# G1000_Arduino_Breakout_and_MCPs.net
KiCad netlist of a schematic drawn in EAGLE
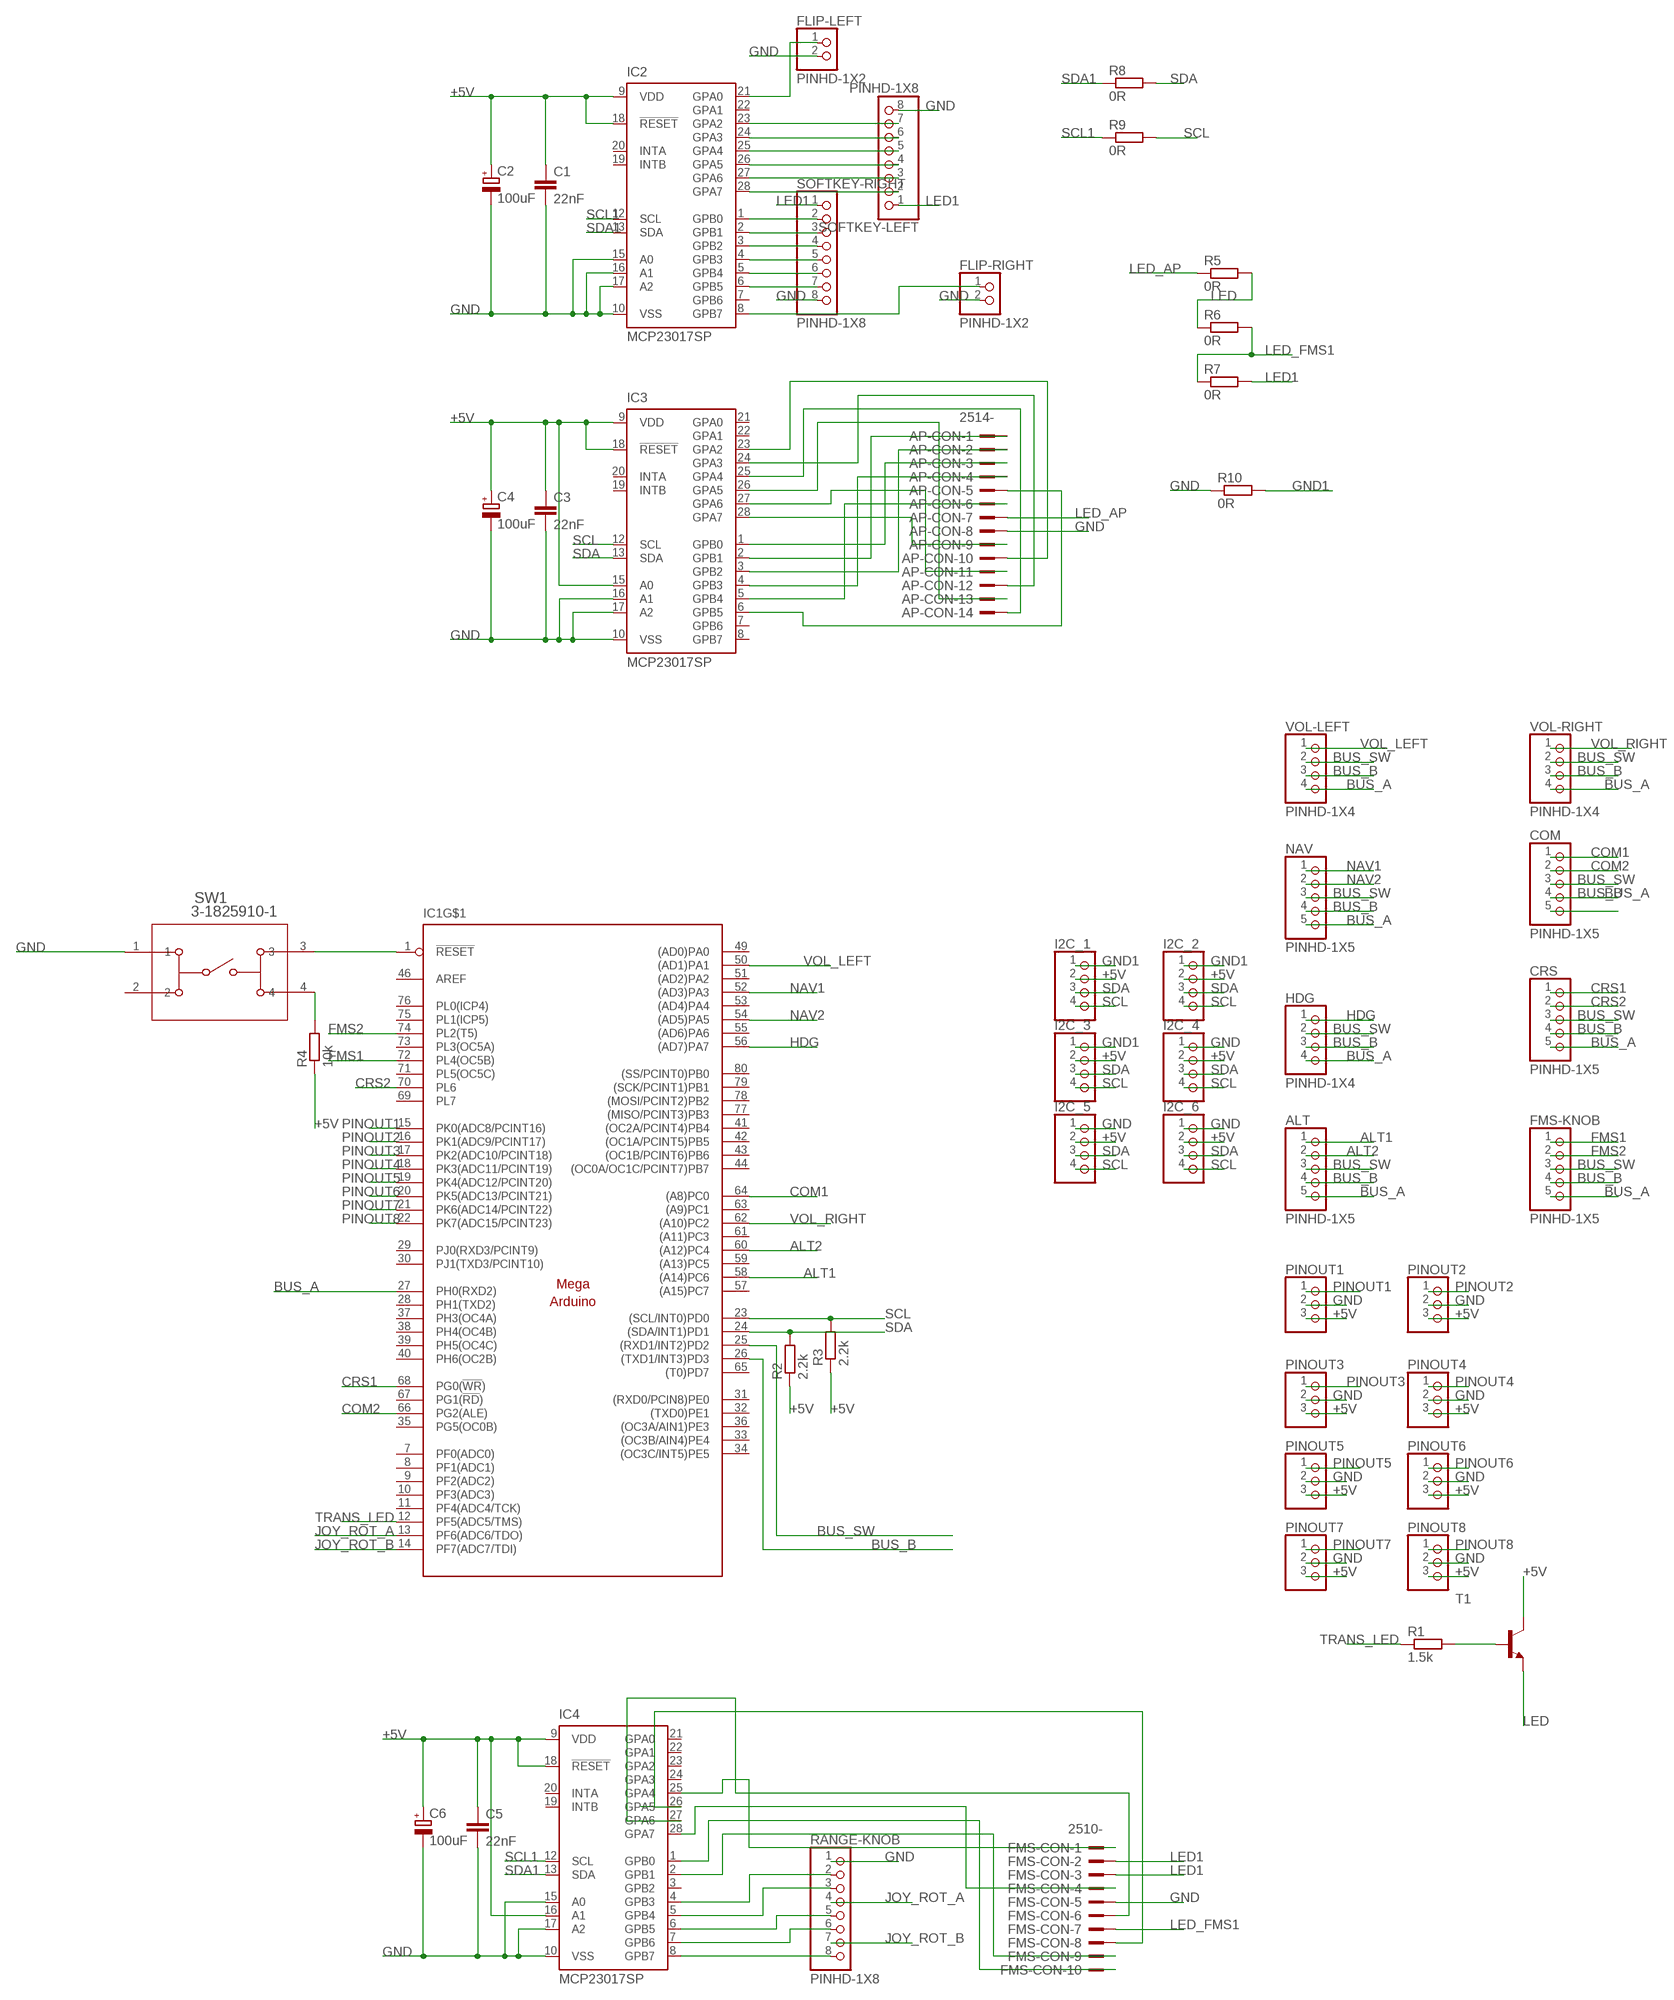
[diagram p0: schematic, sheet 1]

(export (version "E")
  (design (tool "Eeschema 10.0.6"))
  (components
    (comp (ref "ALT")
      (value "PINHD-1X5")
      (footprint "eagle-import:1X05")
      (libsource (lib "eagle-import") (part "PINHD-1X5"))
    )
    (comp (ref "AP-CON")
      (value "2514-")
      (footprint "eagle-import:PAK100_2500-14")
      (libsource (lib "eagle-import") (part "2514-"))
    )
    (comp (ref "C1")
      (value "22nF")
      (footprint "eagle-import:C025-025X050")
      (libsource (lib "eagle-import") (part "C-EU025-025X050"))
    )
    (comp (ref "C2")
      (value "100uF")
      (footprint "eagle-import:E2,5-6")
      (libsource (lib "eagle-import") (part "CPOL-EUE2.5-6"))
    )
    (comp (ref "C3")
      (value "22nF")
      (footprint "eagle-import:C025-025X050")
      (libsource (lib "eagle-import") (part "C-EU025-025X050"))
    )
    (comp (ref "C4")
      (value "100uF")
      (footprint "eagle-import:E2,5-6")
      (libsource (lib "eagle-import") (part "CPOL-EUE2.5-6"))
    )
    (comp (ref "C5")
      (value "22nF")
      (footprint "eagle-import:C025-025X050")
      (libsource (lib "eagle-import") (part "C-EU025-025X050"))
    )
    (comp (ref "C6")
      (value "100uF")
      (footprint "eagle-import:E2,5-6")
      (libsource (lib "eagle-import") (part "CPOL-EUE2.5-6"))
    )
    (comp (ref "COM")
      (value "PINHD-1X5")
      (footprint "eagle-import:1X05")
      (libsource (lib "eagle-import") (part "PINHD-1X5"))
    )
    (comp (ref "CRS")
      (value "PINHD-1X5")
      (footprint "eagle-import:1X05")
      (libsource (lib "eagle-import") (part "PINHD-1X5"))
    )
    (comp (ref "FLIP-LEFT")
      (value "PINHD-1X2")
      (footprint "eagle-import:1X02")
      (libsource (lib "eagle-import") (part "PINHD-1X2"))
    )
    (comp (ref "FLIP-RIGHT")
      (value "PINHD-1X2")
      (footprint "eagle-import:1X02")
      (libsource (lib "eagle-import") (part "PINHD-1X2"))
    )
    (comp (ref "FMS-CON")
      (value "2510-")
      (footprint "eagle-import:PAK100_2500-10")
      (fields (field (name "MF") "3M") (field (name "MPN") "2510-6002UB"))
      (libsource (lib "eagle-import") (part "2510-"))
    )
    (comp (ref "FMS-KNOB")
      (value "PINHD-1X5")
      (footprint "eagle-import:1X05")
      (libsource (lib "eagle-import") (part "PINHD-1X5"))
    )
    (comp (ref "HDG")
      (value "PINHD-1X4")
      (footprint "eagle-import:1X04")
      (libsource (lib "eagle-import") (part "PINHD-1X4"))
    )
    (comp (ref "I2C_1")
      (value "PINHD-1X4")
      (footprint "eagle-import:1X04")
      (libsource (lib "eagle-import") (part "pinhead_325_PINHD-1X4"))
    )
    (comp (ref "I2C_2")
      (value "PINHD-1X4")
      (footprint "eagle-import:1X04")
      (libsource (lib "eagle-import") (part "pinhead_325_PINHD-1X4"))
    )
    (comp (ref "I2C_3")
      (value "PINHD-1X4")
      (footprint "eagle-import:1X04")
      (libsource (lib "eagle-import") (part "pinhead_325_PINHD-1X4"))
    )
    (comp (ref "I2C_4")
      (value "PINHD-1X4")
      (footprint "eagle-import:1X04")
      (libsource (lib "eagle-import") (part "pinhead_325_PINHD-1X4"))
    )
    (comp (ref "I2C_5")
      (value "PINHD-1X4")
      (footprint "eagle-import:1X04")
      (libsource (lib "eagle-import") (part "pinhead_325_PINHD-1X4"))
    )
    (comp (ref "I2C_6")
      (value "PINHD-1X4")
      (footprint "eagle-import:1X04")
      (libsource (lib "eagle-import") (part "pinhead_325_PINHD-1X4"))
    )
    (comp (ref "IC1")
      (value "MEGAARDUINO_22")
      (footprint "eagle-import:MEGA_ARDUINO_2")
      (libsource (lib "eagle-import") (part "MEGAARDUINO_22"))
    )
    (comp (ref "IC2")
      (value "MCP23017SP")
      (footprint "eagle-import:DIL28-3")
      (libsource (lib "eagle-import") (part "MCP23017SP"))
    )
    (comp (ref "IC3")
      (value "MCP23017SP")
      (footprint "eagle-import:DIL28-3")
      (libsource (lib "eagle-import") (part "MCP23017SP"))
    )
    (comp (ref "IC4")
      (value "MCP23017SP")
      (footprint "eagle-import:DIL28-3")
      (libsource (lib "eagle-import") (part "MCP23017SP"))
    )
    (comp (ref "NAV")
      (value "PINHD-1X5")
      (footprint "eagle-import:1X05")
      (libsource (lib "eagle-import") (part "PINHD-1X5"))
    )
    (comp (ref "PINOUT1")
      (value "PINHD-1X3")
      (footprint "eagle-import:1X03")
      (libsource (lib "eagle-import") (part "PINHD-1X3"))
    )
    (comp (ref "PINOUT2")
      (value "PINHD-1X3")
      (footprint "eagle-import:1X03")
      (libsource (lib "eagle-import") (part "PINHD-1X3"))
    )
    (comp (ref "PINOUT3")
      (value "PINHD-1X3")
      (footprint "eagle-import:1X03")
      (libsource (lib "eagle-import") (part "PINHD-1X3"))
    )
    (comp (ref "PINOUT4")
      (value "PINHD-1X3")
      (footprint "eagle-import:1X03")
      (libsource (lib "eagle-import") (part "PINHD-1X3"))
    )
    (comp (ref "PINOUT5")
      (value "PINHD-1X3")
      (footprint "eagle-import:1X03")
      (libsource (lib "eagle-import") (part "PINHD-1X3"))
    )
    (comp (ref "PINOUT6")
      (value "PINHD-1X3")
      (footprint "eagle-import:1X03")
      (libsource (lib "eagle-import") (part "PINHD-1X3"))
    )
    (comp (ref "PINOUT7")
      (value "PINHD-1X3")
      (footprint "eagle-import:1X03")
      (libsource (lib "eagle-import") (part "PINHD-1X3"))
    )
    (comp (ref "PINOUT8")
      (value "PINHD-1X3")
      (footprint "eagle-import:1X03")
      (libsource (lib "eagle-import") (part "PINHD-1X3"))
    )
    (comp (ref "R1")
      (value "1.5k")
      (footprint "eagle-import:0207_10")
      (libsource (lib "eagle-import") (part "R-EU_0207/10"))
    )
    (comp (ref "R2")
      (value "2.2k")
      (footprint "eagle-import:0207_10")
      (libsource (lib "eagle-import") (part "R-EU_0207/10"))
    )
    (comp (ref "R3")
      (value "2.2k")
      (footprint "eagle-import:0207_10")
      (libsource (lib "eagle-import") (part "R-EU_0207/10"))
    )
    (comp (ref "R4")
      (value "10k")
      (footprint "eagle-import:0207_10")
      (libsource (lib "eagle-import") (part "R-EU_0207/10"))
    )
    (comp (ref "R5")
      (value "0R")
      (footprint "eagle-import:0207_10")
      (libsource (lib "eagle-import") (part "R-EU_0207/10"))
    )
    (comp (ref "R6")
      (value "0R")
      (footprint "eagle-import:0207_10")
      (libsource (lib "eagle-import") (part "R-EU_0207/10"))
    )
    (comp (ref "R7")
      (value "0R")
      (footprint "eagle-import:0207_10")
      (libsource (lib "eagle-import") (part "R-EU_0207/10"))
    )
    (comp (ref "R8")
      (value "0R")
      (footprint "eagle-import:0207_10")
      (libsource (lib "eagle-import") (part "R-EU_0207/10"))
    )
    (comp (ref "R9")
      (value "0R")
      (footprint "eagle-import:0207_10")
      (libsource (lib "eagle-import") (part "R-EU_0207/10"))
    )
    (comp (ref "R10")
      (value "0R")
      (footprint "eagle-import:0207_10")
      (libsource (lib "eagle-import") (part "R-EU_0207/10"))
    )
    (comp (ref "RANGE-KNOB")
      (value "PINHD-1X8")
      (footprint "eagle-import:1X08")
      (libsource (lib "eagle-import") (part "PINHD-1X8"))
    )
    (comp (ref "SOFTKEY-LEFT")
      (value "PINHD-1X8")
      (footprint "eagle-import:1X08")
      (libsource (lib "eagle-import") (part "PINHD-1X8"))
    )
    (comp (ref "SOFTKEY-RIGHT")
      (value "PINHD-1X8")
      (footprint "eagle-import:1X08")
      (libsource (lib "eagle-import") (part "PINHD-1X8"))
    )
    (comp (ref "SW1")
      (value "3-1825910-1")
      (footprint "eagle-import:SW4_1825910-H")
      (fields (field (name "COPYRIGHT") "Copyright (C) 2016 Accelerated Designs. All rights reserved"))
      (libsource (lib "eagle-import") (part "3-1825910-1"))
    )
    (comp (ref "T1")
      (value "2N2222-NPN-TO92-EBC")
      (footprint "eagle-import:TO92-EBC")
      (libsource (lib "eagle-import") (part "-NPN-TO92-EBC2N2222"))
    )
    (comp (ref "VOL-LEFT")
      (value "PINHD-1X4")
      (footprint "eagle-import:1X04")
      (libsource (lib "eagle-import") (part "PINHD-1X4"))
    )
    (comp (ref "VOL-RIGHT")
      (value "PINHD-1X4")
      (footprint "eagle-import:1X04")
      (libsource (lib "eagle-import") (part "PINHD-1X4"))
    )
  )
  (nets
    (net (code "1") (name "/+5V") (class "Default")
      (node (ref "C1") (pin "1") (pinfunction "1_1") (pintype "passive"))
      (node (ref "C2") (pin "+") (pinfunction "+_+") (pintype "passive"))
      (node (ref "C3") (pin "1") (pinfunction "1_1") (pintype "passive"))
      (node (ref "C4") (pin "+") (pinfunction "+_+") (pintype "passive"))
      (node (ref "C5") (pin "1") (pinfunction "1_1") (pintype "passive"))
      (node (ref "C6") (pin "+") (pinfunction "+_+") (pintype "passive"))
      (node (ref "I2C_1") (pin "2") (pinfunction "2_2") (pintype "passive"))
      (node (ref "I2C_2") (pin "2") (pinfunction "2_2") (pintype "passive"))
      (node (ref "I2C_3") (pin "2") (pinfunction "2_2") (pintype "passive"))
      (node (ref "I2C_4") (pin "2") (pinfunction "2_2") (pintype "passive"))
      (node (ref "I2C_5") (pin "2") (pinfunction "2_2") (pintype "passive"))
      (node (ref "I2C_6") (pin "2") (pinfunction "2_2") (pintype "passive"))
      (node (ref "IC2") (pin "18") (pinfunction "~{RESET}_18") (pintype "input"))
      (node (ref "IC2") (pin "9") (pinfunction "VDD_9") (pintype "power_in"))
      (node (ref "IC3") (pin "15") (pinfunction "A0_15") (pintype "input"))
      (node (ref "IC3") (pin "18") (pinfunction "~{RESET}_18") (pintype "input"))
      (node (ref "IC3") (pin "9") (pinfunction "VDD_9") (pintype "power_in"))
      (node (ref "IC4") (pin "16") (pinfunction "A1_16") (pintype "input"))
      (node (ref "IC4") (pin "18") (pinfunction "~{RESET}_18") (pintype "input"))
      (node (ref "IC4") (pin "9") (pinfunction "VDD_9") (pintype "power_in"))
      (node (ref "PINOUT1") (pin "3") (pinfunction "3_3") (pintype "passive"))
      (node (ref "PINOUT2") (pin "3") (pinfunction "3_3") (pintype "passive"))
      (node (ref "PINOUT3") (pin "3") (pinfunction "3_3") (pintype "passive"))
      (node (ref "PINOUT4") (pin "3") (pinfunction "3_3") (pintype "passive"))
      (node (ref "PINOUT5") (pin "3") (pinfunction "3_3") (pintype "passive"))
      (node (ref "PINOUT6") (pin "3") (pinfunction "3_3") (pintype "passive"))
      (node (ref "PINOUT7") (pin "3") (pinfunction "3_3") (pintype "passive"))
      (node (ref "PINOUT8") (pin "3") (pinfunction "3_3") (pintype "passive"))
      (node (ref "R2") (pin "1") (pinfunction "1_1") (pintype "passive"))
      (node (ref "R3") (pin "1") (pinfunction "1_1") (pintype "passive"))
      (node (ref "R4") (pin "1") (pinfunction "1_1") (pintype "passive"))
      (node (ref "T1") (pin "C") (pinfunction "C_C") (pintype "passive"))
    )
    (net (code "2") (name "/ALT1") (class "Default")
      (node (ref "ALT") (pin "1") (pinfunction "1_1") (pintype "passive"))
      (node (ref "IC1") (pin "58") (pinfunction "(A14)PC6_58") (pintype "bidirectional"))
    )
    (net (code "3") (name "/ALT2") (class "Default")
      (node (ref "ALT") (pin "2") (pinfunction "2_2") (pintype "passive"))
      (node (ref "IC1") (pin "60") (pinfunction "(A12)PC4_60") (pintype "bidirectional"))
    )
    (net (code "4") (name "/BUS_A") (class "Default")
      (node (ref "ALT") (pin "5") (pinfunction "5_5") (pintype "passive"))
      (node (ref "COM") (pin "5") (pinfunction "5_5") (pintype "passive"))
      (node (ref "CRS") (pin "5") (pinfunction "5_5") (pintype "passive"))
      (node (ref "FMS-KNOB") (pin "5") (pinfunction "5_5") (pintype "passive"))
      (node (ref "HDG") (pin "4") (pinfunction "4_4") (pintype "passive"))
      (node (ref "IC1") (pin "27") (pinfunction "PH0(RXD2)_27") (pintype "bidirectional"))
      (node (ref "NAV") (pin "5") (pinfunction "5_5") (pintype "passive"))
      (node (ref "VOL-LEFT") (pin "4") (pinfunction "4_4") (pintype "passive"))
      (node (ref "VOL-RIGHT") (pin "4") (pinfunction "4_4") (pintype "passive"))
    )
    (net (code "5") (name "/BUS_B") (class "Default")
      (node (ref "ALT") (pin "4") (pinfunction "4_4") (pintype "passive"))
      (node (ref "COM") (pin "4") (pinfunction "4_4") (pintype "passive"))
      (node (ref "CRS") (pin "4") (pinfunction "4_4") (pintype "passive"))
      (node (ref "FMS-KNOB") (pin "4") (pinfunction "4_4") (pintype "passive"))
      (node (ref "HDG") (pin "3") (pinfunction "3_3") (pintype "passive"))
      (node (ref "IC1") (pin "26") (pinfunction "(TXD1/INT3)PD3_26") (pintype "bidirectional"))
      (node (ref "NAV") (pin "4") (pinfunction "4_4") (pintype "passive"))
      (node (ref "VOL-LEFT") (pin "3") (pinfunction "3_3") (pintype "passive"))
      (node (ref "VOL-RIGHT") (pin "3") (pinfunction "3_3") (pintype "passive"))
    )
    (net (code "6") (name "/BUS_SW") (class "Default")
      (node (ref "ALT") (pin "3") (pinfunction "3_3") (pintype "passive"))
      (node (ref "COM") (pin "3") (pinfunction "3_3") (pintype "passive"))
      (node (ref "CRS") (pin "3") (pinfunction "3_3") (pintype "passive"))
      (node (ref "FMS-KNOB") (pin "3") (pinfunction "3_3") (pintype "passive"))
      (node (ref "HDG") (pin "2") (pinfunction "2_2") (pintype "passive"))
      (node (ref "IC1") (pin "25") (pinfunction "(RXD1/INT2)PD2_25") (pintype "bidirectional"))
      (node (ref "NAV") (pin "3") (pinfunction "3_3") (pintype "passive"))
      (node (ref "VOL-LEFT") (pin "2") (pinfunction "2_2") (pintype "passive"))
      (node (ref "VOL-RIGHT") (pin "2") (pinfunction "2_2") (pintype "passive"))
    )
    (net (code "7") (name "/COM1") (class "Default")
      (node (ref "COM") (pin "1") (pinfunction "1_1") (pintype "passive"))
      (node (ref "IC1") (pin "64") (pinfunction "(A8)PC0_64") (pintype "bidirectional"))
    )
    (net (code "8") (name "/COM2") (class "Default")
      (node (ref "COM") (pin "2") (pinfunction "2_2") (pintype "passive"))
      (node (ref "IC1") (pin "66") (pinfunction "PG2(ALE)_66") (pintype "bidirectional"))
    )
    (net (code "9") (name "/CRS1") (class "Default")
      (node (ref "CRS") (pin "1") (pinfunction "1_1") (pintype "passive"))
      (node (ref "IC1") (pin "68") (pinfunction "PG0(~{WR})_68") (pintype "bidirectional"))
    )
    (net (code "10") (name "/CRS2") (class "Default")
      (node (ref "CRS") (pin "2") (pinfunction "2_2") (pintype "passive"))
      (node (ref "IC1") (pin "70") (pinfunction "PL6_70") (pintype "bidirectional"))
    )
    (net (code "11") (name "/FMS1") (class "Default")
      (node (ref "FMS-KNOB") (pin "1") (pinfunction "1_1") (pintype "passive"))
      (node (ref "IC1") (pin "72") (pinfunction "PL4(OC5B)_72") (pintype "bidirectional"))
    )
    (net (code "12") (name "/FMS2") (class "Default")
      (node (ref "FMS-KNOB") (pin "2") (pinfunction "2_2") (pintype "passive"))
      (node (ref "IC1") (pin "74") (pinfunction "PL2(T5)_74") (pintype "bidirectional"))
    )
    (net (code "13") (name "/GND") (class "Default")
      (node (ref "AP-CON") (pin "8") (pinfunction "KL_8") (pintype "passive"))
      (node (ref "C1") (pin "2") (pinfunction "2_2") (pintype "passive"))
      (node (ref "C2") (pin "-") (pinfunction "-_-") (pintype "passive"))
      (node (ref "C3") (pin "2") (pinfunction "2_2") (pintype "passive"))
      (node (ref "C4") (pin "-") (pinfunction "-_-") (pintype "passive"))
      (node (ref "C5") (pin "2") (pinfunction "2_2") (pintype "passive"))
      (node (ref "C6") (pin "-") (pinfunction "-_-") (pintype "passive"))
      (node (ref "FLIP-LEFT") (pin "2") (pinfunction "2_2") (pintype "passive"))
      (node (ref "FLIP-RIGHT") (pin "2") (pinfunction "2_2") (pintype "passive"))
      (node (ref "FMS-CON") (pin "5") (pinfunction "KL_5") (pintype "passive"))
      (node (ref "I2C_4") (pin "1") (pinfunction "1_1") (pintype "passive"))
      (node (ref "I2C_5") (pin "1") (pinfunction "1_1") (pintype "passive"))
      (node (ref "I2C_6") (pin "1") (pinfunction "1_1") (pintype "passive"))
      (node (ref "IC2") (pin "10") (pinfunction "VSS_10") (pintype "power_in"))
      (node (ref "IC2") (pin "15") (pinfunction "A0_15") (pintype "input"))
      (node (ref "IC2") (pin "16") (pinfunction "A1_16") (pintype "input"))
      (node (ref "IC2") (pin "17") (pinfunction "A2_17") (pintype "input"))
      (node (ref "IC3") (pin "10") (pinfunction "VSS_10") (pintype "power_in"))
      (node (ref "IC3") (pin "16") (pinfunction "A1_16") (pintype "input"))
      (node (ref "IC3") (pin "17") (pinfunction "A2_17") (pintype "input"))
      (node (ref "IC4") (pin "10") (pinfunction "VSS_10") (pintype "power_in"))
      (node (ref "IC4") (pin "15") (pinfunction "A0_15") (pintype "input"))
      (node (ref "IC4") (pin "17") (pinfunction "A2_17") (pintype "input"))
      (node (ref "PINOUT1") (pin "2") (pinfunction "2_2") (pintype "passive"))
      (node (ref "PINOUT2") (pin "2") (pinfunction "2_2") (pintype "passive"))
      (node (ref "PINOUT3") (pin "2") (pinfunction "2_2") (pintype "passive"))
      (node (ref "PINOUT4") (pin "2") (pinfunction "2_2") (pintype "passive"))
      (node (ref "PINOUT5") (pin "2") (pinfunction "2_2") (pintype "passive"))
      (node (ref "PINOUT6") (pin "2") (pinfunction "2_2") (pintype "passive"))
      (node (ref "PINOUT7") (pin "2") (pinfunction "2_2") (pintype "passive"))
      (node (ref "PINOUT8") (pin "2") (pinfunction "2_2") (pintype "passive"))
      (node (ref "R10") (pin "1") (pinfunction "1_1") (pintype "passive"))
      (node (ref "RANGE-KNOB") (pin "1") (pinfunction "1_1") (pintype "passive"))
      (node (ref "SOFTKEY-LEFT") (pin "8") (pinfunction "8_8") (pintype "passive"))
      (node (ref "SOFTKEY-RIGHT") (pin "8") (pinfunction "8_8") (pintype "passive"))
      (node (ref "SW1") (pin "1") (pinfunction "1_1") (pintype "passive"))
    )
    (net (code "14") (name "/GND1") (class "Default")
      (node (ref "I2C_1") (pin "1") (pinfunction "1_1") (pintype "passive"))
      (node (ref "I2C_2") (pin "1") (pinfunction "1_1") (pintype "passive"))
      (node (ref "I2C_3") (pin "1") (pinfunction "1_1") (pintype "passive"))
      (node (ref "R10") (pin "2") (pinfunction "2_2") (pintype "passive"))
    )
    (net (code "15") (name "/HDG") (class "Default")
      (node (ref "HDG") (pin "1") (pinfunction "1_1") (pintype "passive"))
      (node (ref "IC1") (pin "56") (pinfunction "(AD7)PA7_56") (pintype "bidirectional"))
    )
    (net (code "16") (name "/JOY_ROT_A") (class "Default")
      (node (ref "IC1") (pin "13") (pinfunction "PF6(ADC6/TDO)_13") (pintype "bidirectional"))
      (node (ref "RANGE-KNOB") (pin "4") (pinfunction "4_4") (pintype "passive"))
    )
    (net (code "17") (name "/JOY_ROT_B") (class "Default")
      (node (ref "IC1") (pin "14") (pinfunction "PF7(ADC7/TDI)_14") (pintype "bidirectional"))
      (node (ref "RANGE-KNOB") (pin "7") (pinfunction "7_7") (pintype "passive"))
    )
    (net (code "18") (name "/LED") (class "Default")
      (node (ref "R5") (pin "2") (pinfunction "2_2") (pintype "passive"))
      (node (ref "R6") (pin "1") (pinfunction "1_1") (pintype "passive"))
      (node (ref "T1") (pin "E") (pinfunction "E_E") (pintype "passive"))
    )
    (net (code "19") (name "/LED1") (class "Default")
      (node (ref "FMS-CON") (pin "2") (pinfunction "KL_2") (pintype "passive"))
      (node (ref "FMS-CON") (pin "3") (pinfunction "KL_3") (pintype "passive"))
      (node (ref "R7") (pin "2") (pinfunction "2_2") (pintype "passive"))
      (node (ref "SOFTKEY-LEFT") (pin "1") (pinfunction "1_1") (pintype "passive"))
      (node (ref "SOFTKEY-RIGHT") (pin "1") (pinfunction "1_1") (pintype "passive"))
    )
    (net (code "20") (name "/LED_AP") (class "Default")
      (node (ref "AP-CON") (pin "7") (pinfunction "KL_7") (pintype "passive"))
      (node (ref "R5") (pin "1") (pinfunction "1_1") (pintype "passive"))
    )
    (net (code "21") (name "/LED_FMS1") (class "Default")
      (node (ref "FMS-CON") (pin "7") (pinfunction "KL_7") (pintype "passive"))
      (node (ref "R6") (pin "2") (pinfunction "2_2") (pintype "passive"))
      (node (ref "R7") (pin "1") (pinfunction "1_1") (pintype "passive"))
    )
    (net (code "22") (name "/NAV1") (class "Default")
      (node (ref "IC1") (pin "52") (pinfunction "(AD3)PA3_52") (pintype "bidirectional"))
      (node (ref "NAV") (pin "1") (pinfunction "1_1") (pintype "passive"))
    )
    (net (code "23") (name "/NAV2") (class "Default")
      (node (ref "IC1") (pin "54") (pinfunction "(AD5)PA5_54") (pintype "bidirectional"))
      (node (ref "NAV") (pin "2") (pinfunction "2_2") (pintype "passive"))
    )
    (net (code "24") (name "/PINOUT1") (class "Default")
      (node (ref "IC1") (pin "15") (pinfunction "PK0(ADC8/PCINT16)_15") (pintype "bidirectional"))
      (node (ref "PINOUT1") (pin "1") (pinfunction "1_1") (pintype "passive"))
    )
    (net (code "25") (name "/PINOUT2") (class "Default")
      (node (ref "IC1") (pin "16") (pinfunction "PK1(ADC9/PCINT17)_16") (pintype "bidirectional"))
      (node (ref "PINOUT2") (pin "1") (pinfunction "1_1") (pintype "passive"))
    )
    (net (code "26") (name "/PINOUT3") (class "Default")
      (node (ref "IC1") (pin "17") (pinfunction "PK2(ADC10/PCINT18)_17") (pintype "bidirectional"))
      (node (ref "PINOUT3") (pin "1") (pinfunction "1_1") (pintype "passive"))
    )
    (net (code "27") (name "/PINOUT4") (class "Default")
      (node (ref "IC1") (pin "18") (pinfunction "PK3(ADC11/PCINT19)_18") (pintype "bidirectional"))
      (node (ref "PINOUT4") (pin "1") (pinfunction "1_1") (pintype "passive"))
    )
    (net (code "28") (name "/PINOUT5") (class "Default")
      (node (ref "IC1") (pin "19") (pinfunction "PK4(ADC12/PCINT20)_19") (pintype "bidirectional"))
      (node (ref "PINOUT5") (pin "1") (pinfunction "1_1") (pintype "passive"))
    )
    (net (code "29") (name "/PINOUT6") (class "Default")
      (node (ref "IC1") (pin "20") (pinfunction "PK5(ADC13/PCINT21)_20") (pintype "bidirectional"))
      (node (ref "PINOUT6") (pin "1") (pinfunction "1_1") (pintype "passive"))
    )
    (net (code "30") (name "/PINOUT7") (class "Default")
      (node (ref "IC1") (pin "21") (pinfunction "PK6(ADC14/PCINT22)_21") (pintype "bidirectional"))
      (node (ref "PINOUT7") (pin "1") (pinfunction "1_1") (pintype "passive"))
    )
    (net (code "31") (name "/PINOUT8") (class "Default")
      (node (ref "IC1") (pin "22") (pinfunction "PK7(ADC15/PCINT23)_22") (pintype "bidirectional"))
      (node (ref "PINOUT8") (pin "1") (pinfunction "1_1") (pintype "passive"))
    )
    (net (code "32") (name "/SCL") (class "Default")
      (node (ref "I2C_1") (pin "4") (pinfunction "4_4") (pintype "passive"))
      (node (ref "I2C_2") (pin "4") (pinfunction "4_4") (pintype "passive"))
      (node (ref "I2C_3") (pin "4") (pinfunction "4_4") (pintype "passive"))
      (node (ref "I2C_4") (pin "4") (pinfunction "4_4") (pintype "passive"))
      (node (ref "I2C_5") (pin "4") (pinfunction "4_4") (pintype "passive"))
      (node (ref "I2C_6") (pin "4") (pinfunction "4_4") (pintype "passive"))
      (node (ref "IC1") (pin "23") (pinfunction "(SCL/INT0)PD0_23") (pintype "bidirectional"))
      (node (ref "IC3") (pin "12") (pinfunction "SCL_12") (pintype "input"))
      (node (ref "R3") (pin "2") (pinfunction "2_2") (pintype "passive"))
      (node (ref "R9") (pin "2") (pinfunction "2_2") (pintype "passive"))
    )
    (net (code "33") (name "/SCL1") (class "Default")
      (node (ref "IC2") (pin "12") (pinfunction "SCL_12") (pintype "input"))
      (node (ref "IC4") (pin "12") (pinfunction "SCL_12") (pintype "input"))
      (node (ref "R9") (pin "1") (pinfunction "1_1") (pintype "passive"))
    )
    (net (code "34") (name "/SDA") (class "Default")
      (node (ref "I2C_1") (pin "3") (pinfunction "3_3") (pintype "passive"))
      (node (ref "I2C_2") (pin "3") (pinfunction "3_3") (pintype "passive"))
      (node (ref "I2C_3") (pin "3") (pinfunction "3_3") (pintype "passive"))
      (node (ref "I2C_4") (pin "3") (pinfunction "3_3") (pintype "passive"))
      (node (ref "I2C_5") (pin "3") (pinfunction "3_3") (pintype "passive"))
      (node (ref "I2C_6") (pin "3") (pinfunction "3_3") (pintype "passive"))
      (node (ref "IC1") (pin "24") (pinfunction "(SDA/INT1)PD1_24") (pintype "bidirectional"))
      (node (ref "IC3") (pin "13") (pinfunction "SDA_13") (pintype "bidirectional"))
      (node (ref "R2") (pin "2") (pinfunction "2_2") (pintype "passive"))
      (node (ref "R8") (pin "2") (pinfunction "2_2") (pintype "passive"))
    )
    (net (code "35") (name "/SDA1") (class "Default")
      (node (ref "IC2") (pin "13") (pinfunction "SDA_13") (pintype "bidirectional"))
      (node (ref "IC4") (pin "13") (pinfunction "SDA_13") (pintype "bidirectional"))
      (node (ref "R8") (pin "1") (pinfunction "1_1") (pintype "passive"))
    )
    (net (code "36") (name "/TRANS_LED") (class "Default")
      (node (ref "IC1") (pin "12") (pinfunction "PF5(ADC5/TMS)_12") (pintype "bidirectional"))
      (node (ref "R1") (pin "1") (pinfunction "1_1") (pintype "passive"))
    )
    (net (code "37") (name "/VOL_LEFT") (class "Default")
      (node (ref "IC1") (pin "50") (pinfunction "(AD1)PA1_50") (pintype "bidirectional"))
      (node (ref "VOL-LEFT") (pin "1") (pinfunction "1_1") (pintype "passive"))
    )
    (net (code "38") (name "/VOL_RIGHT") (class "Default")
      (node (ref "IC1") (pin "62") (pinfunction "(A10)PC2_62") (pintype "bidirectional"))
      (node (ref "VOL-RIGHT") (pin "1") (pinfunction "1_1") (pintype "passive"))
    )
    (net (code "39") (name "Net-(AP-CONA-KL)") (class "Default")
      (node (ref "AP-CON") (pin "1") (pinfunction "KL_1") (pintype "passive"))
      (node (ref "IC3") (pin "2") (pinfunction "GPB1_2") (pintype "bidirectional"))
    )
    (net (code "40") (name "Net-(AP-CONB-KL)") (class "Default")
      (node (ref "AP-CON") (pin "10") (pinfunction "KL_10") (pintype "passive"))
      (node (ref "IC3") (pin "23") (pinfunction "GPA2_23") (pintype "bidirectional"))
    )
    (net (code "41") (name "Net-(AP-CONC-KL)") (class "Default")
      (node (ref "AP-CON") (pin "11") (pinfunction "KL_11") (pintype "passive"))
      (node (ref "IC3") (pin "27") (pinfunction "GPA6_27") (pintype "bidirectional"))
    )
    (net (code "42") (name "Net-(AP-COND-KL)") (class "Default")
      (node (ref "AP-CON") (pin "12") (pinfunction "KL_12") (pintype "passive"))
      (node (ref "IC3") (pin "24") (pinfunction "GPA3_24") (pintype "bidirectional"))
    )
    (net (code "43") (name "Net-(AP-CONE-KL)") (class "Default")
      (node (ref "AP-CON") (pin "13") (pinfunction "KL_13") (pintype "passive"))
      (node (ref "IC3") (pin "26") (pinfunction "GPA5_26") (pintype "bidirectional"))
    )
    (net (code "44") (name "Net-(AP-CONF-KL)") (class "Default")
      (node (ref "AP-CON") (pin "14") (pinfunction "KL_14") (pintype "passive"))
      (node (ref "IC3") (pin "25") (pinfunction "GPA4_25") (pintype "bidirectional"))
    )
    (net (code "45") (name "Net-(AP-CONG-KL)") (class "Default")
      (node (ref "AP-CON") (pin "2") (pinfunction "KL_2") (pintype "passive"))
      (node (ref "IC3") (pin "3") (pinfunction "GPB2_3") (pintype "bidirectional"))
    )
    (net (code "46") (name "Net-(AP-CONH-KL)") (class "Default")
      (node (ref "AP-CON") (pin "3") (pinfunction "KL_3") (pintype "passive"))
      (node (ref "IC3") (pin "1") (pinfunction "GPB0_1") (pintype "bidirectional"))
    )
    (net (code "47") (name "Net-(AP-CONI-KL)") (class "Default")
      (node (ref "AP-CON") (pin "4") (pinfunction "KL_4") (pintype "passive"))
      (node (ref "IC3") (pin "4") (pinfunction "GPB3_4") (pintype "bidirectional"))
    )
    (net (code "48") (name "Net-(AP-CONJ-KL)") (class "Default")
      (node (ref "AP-CON") (pin "5") (pinfunction "KL_5") (pintype "passive"))
      (node (ref "IC3") (pin "6") (pinfunction "GPB5_6") (pintype "bidirectional"))
    )
    (net (code "49") (name "Net-(AP-CONK-KL)") (class "Default")
      (node (ref "AP-CON") (pin "6") (pinfunction "KL_6") (pintype "passive"))
      (node (ref "IC3") (pin "5") (pinfunction "GPB4_5") (pintype "bidirectional"))
    )
    (net (code "50") (name "Net-(AP-CONN-KL)") (class "Default")
      (node (ref "AP-CON") (pin "9") (pinfunction "KL_9") (pintype "passive"))
      (node (ref "IC3") (pin "28") (pinfunction "GPA7_28") (pintype "bidirectional"))
    )
    (net (code "51") (name "Net-(FMS-CONA-KL)") (class "Default")
      (node (ref "FMS-CON") (pin "1") (pinfunction "KL_1") (pintype "passive"))
      (node (ref "IC4") (pin "25") (pinfunction "GPA4_25") (pintype "bidirectional"))
    )
    (net (code "52") (name "Net-(FMS-CONB-KL)") (class "Default")
      (node (ref "FMS-CON") (pin "10") (pinfunction "KL_10") (pintype "passive"))
      (node (ref "IC4") (pin "1") (pinfunction "GPB0_1") (pintype "bidirectional"))
    )
    (net (code "53") (name "Net-(FMS-CONE-KL)") (class "Default")
      (node (ref "FMS-CON") (pin "4") (pinfunction "KL_4") (pintype "passive"))
      (node (ref "IC4") (pin "28") (pinfunction "GPA7_28") (pintype "bidirectional"))
    )
    (net (code "54") (name "Net-(FMS-CONG-KL)") (class "Default")
      (node (ref "FMS-CON") (pin "6") (pinfunction "KL_6") (pintype "passive"))
      (node (ref "IC4") (pin "27") (pinfunction "GPA6_27") (pintype "bidirectional"))
    )
    (net (code "55") (name "Net-(FMS-CONI-KL)") (class "Default")
      (node (ref "FMS-CON") (pin "8") (pinfunction "KL_8") (pintype "passive"))
      (node (ref "IC4") (pin "26") (pinfunction "GPA5_26") (pintype "bidirectional"))
    )
    (net (code "56") (name "Net-(FMS-CONJ-KL)") (class "Default")
      (node (ref "FMS-CON") (pin "9") (pinfunction "KL_9") (pintype "passive"))
      (node (ref "IC4") (pin "2") (pinfunction "GPB1_2") (pintype "bidirectional"))
    )
    (net (code "57") (name "Net-(IC1A-~{RESET})") (class "Default")
      (node (ref "IC1") (pin "1") (pinfunction "~{RESET}_1") (pintype "bidirectional"))
      (node (ref "SW1") (pin "3") (pinfunction "3_3") (pintype "passive"))
    )
    (net (code "58") (name "Net-(IC2-GPA0)") (class "Default")
      (node (ref "FLIP-LEFT") (pin "1") (pinfunction "1_1") (pintype "passive"))
      (node (ref "IC2") (pin "21") (pinfunction "GPA0_21") (pintype "bidirectional"))
    )
    (net (code "59") (name "Net-(IC2-GPA2)") (class "Default")
      (node (ref "IC2") (pin "23") (pinfunction "GPA2_23") (pintype "bidirectional"))
      (node (ref "SOFTKEY-LEFT") (pin "7") (pinfunction "7_7") (pintype "passive"))
    )
    (net (code "60") (name "Net-(IC2-GPA3)") (class "Default")
      (node (ref "IC2") (pin "24") (pinfunction "GPA3_24") (pintype "bidirectional"))
      (node (ref "SOFTKEY-LEFT") (pin "6") (pinfunction "6_6") (pintype "passive"))
    )
    (net (code "61") (name "Net-(IC2-GPA4)") (class "Default")
      (node (ref "IC2") (pin "25") (pinfunction "GPA4_25") (pintype "bidirectional"))
      (node (ref "SOFTKEY-LEFT") (pin "5") (pinfunction "5_5") (pintype "passive"))
    )
    (net (code "62") (name "Net-(IC2-GPA5)") (class "Default")
      (node (ref "IC2") (pin "26") (pinfunction "GPA5_26") (pintype "bidirectional"))
      (node (ref "SOFTKEY-LEFT") (pin "4") (pinfunction "4_4") (pintype "passive"))
    )
    (net (code "63") (name "Net-(IC2-GPA6)") (class "Default")
      (node (ref "IC2") (pin "27") (pinfunction "GPA6_27") (pintype "bidirectional"))
      (node (ref "SOFTKEY-LEFT") (pin "3") (pinfunction "3_3") (pintype "passive"))
    )
    (net (code "64") (name "Net-(IC2-GPA7)") (class "Default")
      (node (ref "IC2") (pin "28") (pinfunction "GPA7_28") (pintype "bidirectional"))
      (node (ref "SOFTKEY-LEFT") (pin "2") (pinfunction "2_2") (pintype "passive"))
    )
    (net (code "65") (name "Net-(IC2-GPB0)") (class "Default")
      (node (ref "IC2") (pin "1") (pinfunction "GPB0_1") (pintype "bidirectional"))
      (node (ref "SOFTKEY-RIGHT") (pin "2") (pinfunction "2_2") (pintype "passive"))
    )
    (net (code "66") (name "Net-(IC2-GPB1)") (class "Default")
      (node (ref "IC2") (pin "2") (pinfunction "GPB1_2") (pintype "bidirectional"))
      (node (ref "SOFTKEY-RIGHT") (pin "3") (pinfunction "3_3") (pintype "passive"))
    )
    (net (code "67") (name "Net-(IC2-GPB2)") (class "Default")
      (node (ref "IC2") (pin "3") (pinfunction "GPB2_3") (pintype "bidirectional"))
      (node (ref "SOFTKEY-RIGHT") (pin "4") (pinfunction "4_4") (pintype "passive"))
    )
    (net (code "68") (name "Net-(IC2-GPB3)") (class "Default")
      (node (ref "IC2") (pin "4") (pinfunction "GPB3_4") (pintype "bidirectional"))
      (node (ref "SOFTKEY-RIGHT") (pin "5") (pinfunction "5_5") (pintype "passive"))
    )
    (net (code "69") (name "Net-(IC2-GPB4)") (class "Default")
      (node (ref "IC2") (pin "5") (pinfunction "GPB4_5") (pintype "bidirectional"))
      (node (ref "SOFTKEY-RIGHT") (pin "6") (pinfunction "6_6") (pintype "passive"))
    )
    (net (code "70") (name "Net-(IC2-GPB5)") (class "Default")
      (node (ref "IC2") (pin "6") (pinfunction "GPB5_6") (pintype "bidirectional"))
      (node (ref "SOFTKEY-RIGHT") (pin "7") (pinfunction "7_7") (pintype "passive"))
    )
    (net (code "71") (name "Net-(IC2-GPB7)") (class "Default")
      (node (ref "FLIP-RIGHT") (pin "1") (pinfunction "1_1") (pintype "passive"))
      (node (ref "IC2") (pin "8") (pinfunction "GPB7_8") (pintype "bidirectional"))
    )
    (net (code "72") (name "Net-(IC4-GPB3)") (class "Default")
      (node (ref "IC4") (pin "4") (pinfunction "GPB3_4") (pintype "bidirectional"))
      (node (ref "RANGE-KNOB") (pin "2") (pinfunction "2_2") (pintype "passive"))
    )
    (net (code "73") (name "Net-(IC4-GPB4)") (class "Default")
      (node (ref "IC4") (pin "5") (pinfunction "GPB4_5") (pintype "bidirectional"))
      (node (ref "RANGE-KNOB") (pin "3") (pinfunction "3_3") (pintype "passive"))
    )
    (net (code "74") (name "Net-(IC4-GPB5)") (class "Default")
      (node (ref "IC4") (pin "6") (pinfunction "GPB5_6") (pintype "bidirectional"))
      (node (ref "RANGE-KNOB") (pin "5") (pinfunction "5_5") (pintype "passive"))
    )
    (net (code "75") (name "Net-(IC4-GPB6)") (class "Default")
      (node (ref "IC4") (pin "7") (pinfunction "GPB6_7") (pintype "bidirectional"))
      (node (ref "RANGE-KNOB") (pin "6") (pinfunction "6_6") (pintype "passive"))
    )
    (net (code "76") (name "Net-(IC4-GPB7)") (class "Default")
      (node (ref "IC4") (pin "8") (pinfunction "GPB7_8") (pintype "bidirectional"))
      (node (ref "RANGE-KNOB") (pin "8") (pinfunction "8_8") (pintype "passive"))
    )
    (net (code "77") (name "Net-(R1-Pad2)") (class "Default")
      (node (ref "R1") (pin "2") (pinfunction "2_2") (pintype "passive"))
      (node (ref "T1") (pin "B") (pinfunction "B_B") (pintype "passive"))
    )
    (net (code "78") (name "Net-(R4-Pad2)") (class "Default")
      (node (ref "R4") (pin "2") (pinfunction "2_2") (pintype "passive"))
      (node (ref "SW1") (pin "4") (pinfunction "4_4") (pintype "passive"))
    )
    (net (code "79") (name "unconnected-(IC1A-(A9)PC1-Pad63)") (class "Default")
      (node (ref "IC1") (pin "63") (pinfunction "(A9)PC1_63") (pintype "bidirectional"))
    )
    (net (code "80") (name "unconnected-(IC1A-(A11)PC3-Pad61)") (class "Default")
      (node (ref "IC1") (pin "61") (pinfunction "(A11)PC3_61") (pintype "bidirectional"))
    )
    (net (code "81") (name "unconnected-(IC1A-(A13)PC5-Pad59)") (class "Default")
      (node (ref "IC1") (pin "59") (pinfunction "(A13)PC5_59") (pintype "bidirectional"))
    )
    (net (code "82") (name "unconnected-(IC1A-(A15)PC7-Pad57)") (class "Default")
      (node (ref "IC1") (pin "57") (pinfunction "(A15)PC7_57") (pintype "bidirectional"))
    )
    (net (code "83") (name "unconnected-(IC1A-(AD0)PA0-Pad49)") (class "Default")
      (node (ref "IC1") (pin "49") (pinfunction "(AD0)PA0_49") (pintype "bidirectional"))
    )
    (net (code "84") (name "unconnected-(IC1A-(AD2)PA2-Pad51)") (class "Default")
      (node (ref "IC1") (pin "51") (pinfunction "(AD2)PA2_51") (pintype "bidirectional"))
    )
    (net (code "85") (name "unconnected-(IC1A-(AD4)PA4-Pad53)") (class "Default")
      (node (ref "IC1") (pin "53") (pinfunction "(AD4)PA4_53") (pintype "bidirectional"))
    )
    (net (code "86") (name "unconnected-(IC1A-(AD6)PA6-Pad55)") (class "Default")
      (node (ref "IC1") (pin "55") (pinfunction "(AD6)PA6_55") (pintype "bidirectional"))
    )
    (net (code "87") (name "unconnected-(IC1A-(MISO{slash}PCINT3)PB3-Pad77)") (class "Default")
      (node (ref "IC1") (pin "77") (pinfunction "(MISO/PCINT3)PB3_77") (pintype "bidirectional"))
    )
    (net (code "88") (name "unconnected-(IC1A-(MOSI{slash}PCINT2)PB2-Pad78)") (class "Default")
      (node (ref "IC1") (pin "78") (pinfunction "(MOSI/PCINT2)PB2_78") (pintype "bidirectional"))
    )
    (net (code "89") (name "unconnected-(IC1A-(OC0A{slash}OC1C{slash}PCINT7)PB7-Pad44)") (class "Default")
      (node (ref "IC1") (pin "44") (pinfunction "(OC0A/OC1C/PCINT7)PB7_44") (pintype "bidirectional"))
    )
    (net (code "90") (name "unconnected-(IC1A-(OC1A{slash}PCINT5)PB5-Pad42)") (class "Default")
      (node (ref "IC1") (pin "42") (pinfunction "(OC1A/PCINT5)PB5_42") (pintype "bidirectional"))
    )
    (net (code "91") (name "unconnected-(IC1A-(OC1B{slash}PCINT6)PB6-Pad43)") (class "Default")
      (node (ref "IC1") (pin "43") (pinfunction "(OC1B/PCINT6)PB6_43") (pintype "bidirectional"))
    )
    (net (code "92") (name "unconnected-(IC1A-(OC2A{slash}PCINT4)PB4-Pad41)") (class "Default")
      (node (ref "IC1") (pin "41") (pinfunction "(OC2A/PCINT4)PB4_41") (pintype "bidirectional"))
    )
    (net (code "93") (name "unconnected-(IC1A-(OC3A{slash}AIN1)PE3-Pad36)") (class "Default")
      (node (ref "IC1") (pin "36") (pinfunction "(OC3A/AIN1)PE3_36") (pintype "bidirectional"))
    )
    (net (code "94") (name "unconnected-(IC1A-(OC3B{slash}AIN4)PE4-Pad33)") (class "Default")
      (node (ref "IC1") (pin "33") (pinfunction "(OC3B/AIN4)PE4_33") (pintype "bidirectional"))
    )
    (net (code "95") (name "unconnected-(IC1A-(OC3C{slash}INT5)PE5-Pad34)") (class "Default")
      (node (ref "IC1") (pin "34") (pinfunction "(OC3C/INT5)PE5_34") (pintype "bidirectional"))
    )
    (net (code "96") (name "unconnected-(IC1A-(RXD0{slash}PCIN8)PE0-Pad31)") (class "Default")
      (node (ref "IC1") (pin "31") (pinfunction "(RXD0/PCIN8)PE0_31") (pintype "bidirectional"))
    )
    (net (code "97") (name "unconnected-(IC1A-(SCK{slash}PCINT1)PB1-Pad79)") (class "Default")
      (node (ref "IC1") (pin "79") (pinfunction "(SCK/PCINT1)PB1_79") (pintype "bidirectional"))
    )
    (net (code "98") (name "unconnected-(IC1A-(SS{slash}PCINT0)PB0-Pad80)") (class "Default")
      (node (ref "IC1") (pin "80") (pinfunction "(SS/PCINT0)PB0_80") (pintype "bidirectional"))
    )
    (net (code "99") (name "unconnected-(IC1A-(T0)PD7-Pad65)") (class "Default")
      (node (ref "IC1") (pin "65") (pinfunction "(T0)PD7_65") (pintype "bidirectional"))
    )
    (net (code "100") (name "unconnected-(IC1A-(TXD0)PE1-Pad32)") (class "Default")
      (node (ref "IC1") (pin "32") (pinfunction "(TXD0)PE1_32") (pintype "bidirectional"))
    )
    (net (code "101") (name "unconnected-(IC1A-AREF-Pad46)") (class "Default")
      (node (ref "IC1") (pin "46") (pinfunction "AREF_46") (pintype "bidirectional"))
    )
    (net (code "102") (name "unconnected-(IC1A-PF0(ADC0)-Pad7)") (class "Default")
      (node (ref "IC1") (pin "7") (pinfunction "PF0(ADC0)_7") (pintype "bidirectional"))
    )
    (net (code "103") (name "unconnected-(IC1A-PF1(ADC1)-Pad8)") (class "Default")
      (node (ref "IC1") (pin "8") (pinfunction "PF1(ADC1)_8") (pintype "bidirectional"))
    )
    (net (code "104") (name "unconnected-(IC1A-PF2(ADC2)-Pad9)") (class "Default")
      (node (ref "IC1") (pin "9") (pinfunction "PF2(ADC2)_9") (pintype "bidirectional"))
    )
    (net (code "105") (name "unconnected-(IC1A-PF3(ADC3)-Pad10)") (class "Default")
      (node (ref "IC1") (pin "10") (pinfunction "PF3(ADC3)_10") (pintype "bidirectional"))
    )
    (net (code "106") (name "unconnected-(IC1A-PF4(ADC4{slash}TCK)-Pad11)") (class "Default")
      (node (ref "IC1") (pin "11") (pinfunction "PF4(ADC4/TCK)_11") (pintype "bidirectional"))
    )
    (net (code "107") (name "unconnected-(IC1A-PG1(~{RD})-Pad67)") (class "Default")
      (node (ref "IC1") (pin "67") (pinfunction "PG1(~{RD})_67") (pintype "bidirectional"))
    )
    (net (code "108") (name "unconnected-(IC1A-PG5(OC0B)-Pad35)") (class "Default")
      (node (ref "IC1") (pin "35") (pinfunction "PG5(OC0B)_35") (pintype "bidirectional"))
    )
    (net (code "109") (name "unconnected-(IC1A-PH1(TXD2)-Pad28)") (class "Default")
      (node (ref "IC1") (pin "28") (pinfunction "PH1(TXD2)_28") (pintype "bidirectional"))
    )
    (net (code "110") (name "unconnected-(IC1A-PH3(OC4A)-Pad37)") (class "Default")
      (node (ref "IC1") (pin "37") (pinfunction "PH3(OC4A)_37") (pintype "bidirectional"))
    )
    (net (code "111") (name "unconnected-(IC1A-PH4(OC4B)-Pad38)") (class "Default")
      (node (ref "IC1") (pin "38") (pinfunction "PH4(OC4B)_38") (pintype "bidirectional"))
    )
    (net (code "112") (name "unconnected-(IC1A-PH5(OC4C)-Pad39)") (class "Default")
      (node (ref "IC1") (pin "39") (pinfunction "PH5(OC4C)_39") (pintype "bidirectional"))
    )
    (net (code "113") (name "unconnected-(IC1A-PH6(OC2B)-Pad40)") (class "Default")
      (node (ref "IC1") (pin "40") (pinfunction "PH6(OC2B)_40") (pintype "bidirectional"))
    )
    (net (code "114") (name "unconnected-(IC1A-PJ0(RXD3{slash}PCINT9)-Pad29)") (class "Default")
      (node (ref "IC1") (pin "29") (pinfunction "PJ0(RXD3/PCINT9)_29") (pintype "bidirectional"))
    )
    (net (code "115") (name "unconnected-(IC1A-PJ1(TXD3{slash}PCINT10)-Pad30)") (class "Default")
      (node (ref "IC1") (pin "30") (pinfunction "PJ1(TXD3/PCINT10)_30") (pintype "bidirectional"))
    )
    (net (code "116") (name "unconnected-(IC1A-PL0(ICP4)-Pad76)") (class "Default")
      (node (ref "IC1") (pin "76") (pinfunction "PL0(ICP4)_76") (pintype "bidirectional"))
    )
    (net (code "117") (name "unconnected-(IC1A-PL1(ICP5)-Pad75)") (class "Default")
      (node (ref "IC1") (pin "75") (pinfunction "PL1(ICP5)_75") (pintype "bidirectional"))
    )
    (net (code "118") (name "unconnected-(IC1A-PL3(OC5A)-Pad73)") (class "Default")
      (node (ref "IC1") (pin "73") (pinfunction "PL3(OC5A)_73") (pintype "bidirectional"))
    )
    (net (code "119") (name "unconnected-(IC1A-PL5(OC5C)-Pad71)") (class "Default")
      (node (ref "IC1") (pin "71") (pinfunction "PL5(OC5C)_71") (pintype "bidirectional"))
    )
    (net (code "120") (name "unconnected-(IC1A-PL7-Pad69)") (class "Default")
      (node (ref "IC1") (pin "69") (pinfunction "PL7_69") (pintype "bidirectional"))
    )
    (net (code "121") (name "unconnected-(IC2-GPA1-Pad22)") (class "Default")
      (node (ref "IC2") (pin "22") (pinfunction "GPA1_22") (pintype "bidirectional"))
    )
    (net (code "122") (name "unconnected-(IC2-GPB6-Pad7)") (class "Default")
      (node (ref "IC2") (pin "7") (pinfunction "GPB6_7") (pintype "bidirectional"))
    )
    (net (code "123") (name "unconnected-(IC2-INTA-Pad20)") (class "Default")
      (node (ref "IC2") (pin "20") (pinfunction "INTA_20") (pintype "output"))
    )
    (net (code "124") (name "unconnected-(IC2-INTB-Pad19)") (class "Default")
      (node (ref "IC2") (pin "19") (pinfunction "INTB_19") (pintype "output"))
    )
    (net (code "125") (name "unconnected-(IC3-GPA0-Pad21)") (class "Default")
      (node (ref "IC3") (pin "21") (pinfunction "GPA0_21") (pintype "bidirectional"))
    )
    (net (code "126") (name "unconnected-(IC3-GPA1-Pad22)") (class "Default")
      (node (ref "IC3") (pin "22") (pinfunction "GPA1_22") (pintype "bidirectional"))
    )
    (net (code "127") (name "unconnected-(IC3-GPB6-Pad7)") (class "Default")
      (node (ref "IC3") (pin "7") (pinfunction "GPB6_7") (pintype "bidirectional"))
    )
    (net (code "128") (name "unconnected-(IC3-GPB7-Pad8)") (class "Default")
      (node (ref "IC3") (pin "8") (pinfunction "GPB7_8") (pintype "bidirectional"))
    )
    (net (code "129") (name "unconnected-(IC3-INTA-Pad20)") (class "Default")
      (node (ref "IC3") (pin "20") (pinfunction "INTA_20") (pintype "output"))
    )
    (net (code "130") (name "unconnected-(IC3-INTB-Pad19)") (class "Default")
      (node (ref "IC3") (pin "19") (pinfunction "INTB_19") (pintype "output"))
    )
    (net (code "131") (name "unconnected-(IC4-GPA0-Pad21)") (class "Default")
      (node (ref "IC4") (pin "21") (pinfunction "GPA0_21") (pintype "bidirectional"))
    )
    (net (code "132") (name "unconnected-(IC4-GPA1-Pad22)") (class "Default")
      (node (ref "IC4") (pin "22") (pinfunction "GPA1_22") (pintype "bidirectional"))
    )
    (net (code "133") (name "unconnected-(IC4-GPA2-Pad23)") (class "Default")
      (node (ref "IC4") (pin "23") (pinfunction "GPA2_23") (pintype "bidirectional"))
    )
    (net (code "134") (name "unconnected-(IC4-GPA3-Pad24)") (class "Default")
      (node (ref "IC4") (pin "24") (pinfunction "GPA3_24") (pintype "bidirectional"))
    )
    (net (code "135") (name "unconnected-(IC4-GPB2-Pad3)") (class "Default")
      (node (ref "IC4") (pin "3") (pinfunction "GPB2_3") (pintype "bidirectional"))
    )
    (net (code "136") (name "unconnected-(IC4-INTA-Pad20)") (class "Default")
      (node (ref "IC4") (pin "20") (pinfunction "INTA_20") (pintype "output"))
    )
    (net (code "137") (name "unconnected-(IC4-INTB-Pad19)") (class "Default")
      (node (ref "IC4") (pin "19") (pinfunction "INTB_19") (pintype "output"))
    )
    (net (code "138") (name "unconnected-(SW1-Pad2)") (class "Default")
      (node (ref "SW1") (pin "2") (pinfunction "2_2") (pintype "passive"))
    )
  )
)
